# EMG_rev_I.net
KiCad netlist of a schematic drawn in EAGLE
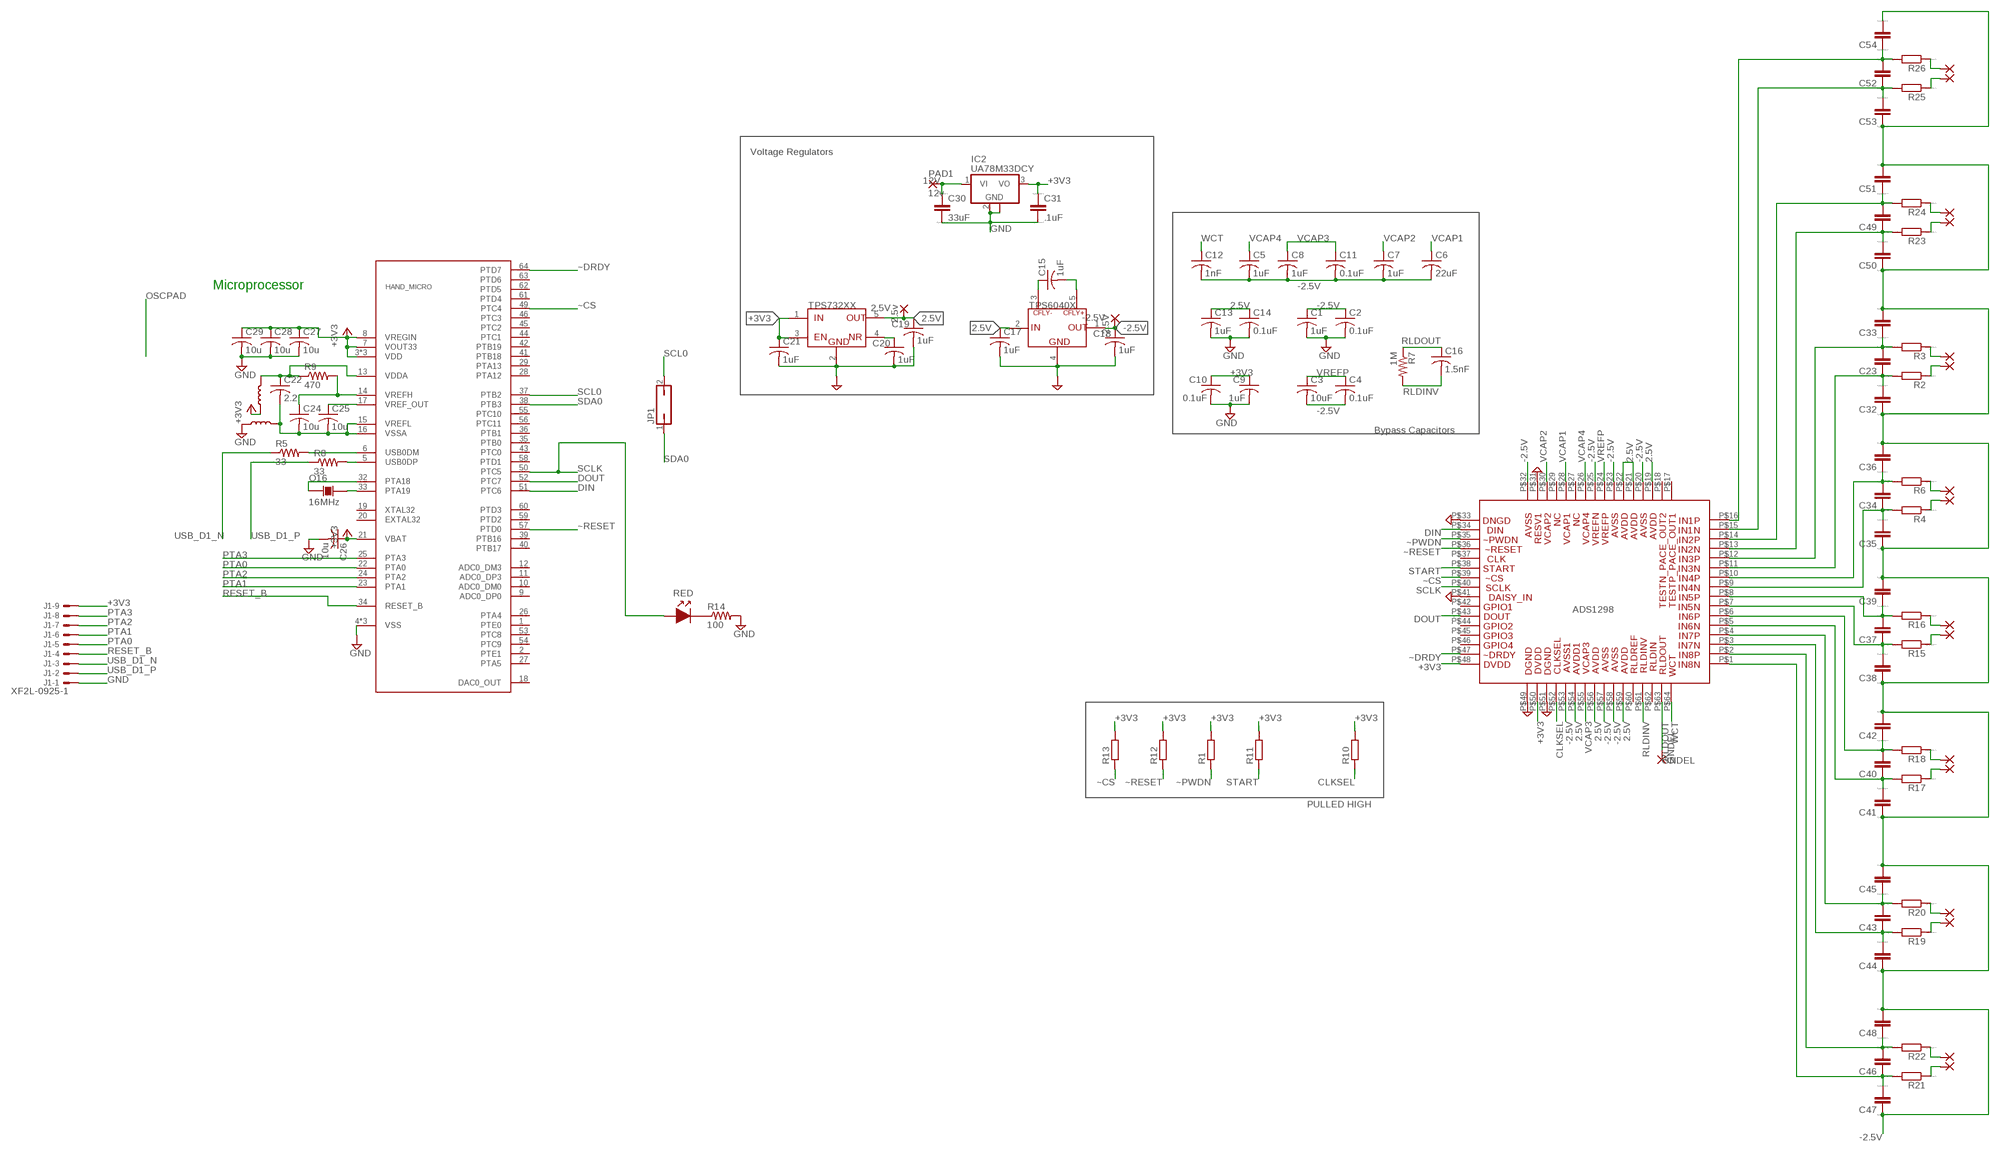
[diagram p0: schematic, sheet 1]

(export (version "E")
  (design (tool "Eeschema 10.0.6"))
  (components
    (comp (ref "-2.5V")
      (value "-2.5V")
      (footprint "eagle-import:2,54_0,9")
      (libsource (lib "eagle-import") (part "2,54/0,9"))
    )
    (comp (ref "2.5V")
      (value "2.5v")
      (footprint "eagle-import:2,54_0,9")
      (libsource (lib "eagle-import") (part "2,54/0,9"))
    )
    (comp (ref "C1")
      (value "1uF")
      (footprint "eagle-import:C0603")
      (libsource (lib "eagle-import") (part "C-USC0603"))
    )
    (comp (ref "C2")
      (value "0.1uF")
      (footprint "eagle-import:C0603")
      (libsource (lib "eagle-import") (part "C-USC0603"))
    )
    (comp (ref "C3")
      (value "10uF")
      (footprint "eagle-import:C0603")
      (libsource (lib "eagle-import") (part "C-USC0603"))
    )
    (comp (ref "C4")
      (value "0.1uF")
      (footprint "eagle-import:C0603")
      (libsource (lib "eagle-import") (part "C-USC0603"))
    )
    (comp (ref "C5")
      (value "1uF")
      (footprint "eagle-import:C0603")
      (libsource (lib "eagle-import") (part "C-USC0603"))
    )
    (comp (ref "C6")
      (value "22uF")
      (footprint "eagle-import:C0603")
      (libsource (lib "eagle-import") (part "C-USC0603"))
    )
    (comp (ref "C7")
      (value "1uF")
      (footprint "eagle-import:C0603")
      (libsource (lib "eagle-import") (part "C-USC0603"))
    )
    (comp (ref "C8")
      (value "1uF")
      (footprint "eagle-import:C0603")
      (libsource (lib "eagle-import") (part "C-USC0603"))
    )
    (comp (ref "C9")
      (value "1uF")
      (footprint "eagle-import:C0603")
      (libsource (lib "eagle-import") (part "C-USC0603"))
    )
    (comp (ref "C10")
      (value "0.1uF")
      (footprint "eagle-import:C0603")
      (libsource (lib "eagle-import") (part "C-USC0603"))
    )
    (comp (ref "C11")
      (value "0.1uF")
      (footprint "eagle-import:C0603")
      (libsource (lib "eagle-import") (part "C-USC0603"))
    )
    (comp (ref "C12")
      (value "1nF")
      (footprint "eagle-import:C0603")
      (libsource (lib "eagle-import") (part "C-USC0603"))
    )
    (comp (ref "C13")
      (value "1uF")
      (footprint "eagle-import:C0603")
      (libsource (lib "eagle-import") (part "C-USC0603"))
    )
    (comp (ref "C14")
      (value "0.1uF")
      (footprint "eagle-import:C0603")
      (libsource (lib "eagle-import") (part "C-USC0603"))
    )
    (comp (ref "C15")
      (value "1uF")
      (footprint "eagle-import:C0603")
      (libsource (lib "eagle-import") (part "C-USC0603"))
    )
    (comp (ref "C16")
      (value "1.5nF")
      (footprint "eagle-import:C0603")
      (libsource (lib "eagle-import") (part "C-USC0603"))
    )
    (comp (ref "C17")
      (value "1uF")
      (footprint "eagle-import:C0603")
      (libsource (lib "eagle-import") (part "C-USC0603"))
    )
    (comp (ref "C18")
      (value "1uF")
      (footprint "eagle-import:C0603")
      (libsource (lib "eagle-import") (part "C-USC0603"))
    )
    (comp (ref "C19")
      (value "1uF")
      (footprint "eagle-import:C0603")
      (libsource (lib "eagle-import") (part "C-USC0603"))
    )
    (comp (ref "C20")
      (value "1uF")
      (footprint "eagle-import:C0603")
      (libsource (lib "eagle-import") (part "C-USC0603"))
    )
    (comp (ref "C21")
      (value "1uF")
      (footprint "eagle-import:C0603")
      (libsource (lib "eagle-import") (part "C-USC0603"))
    )
    (comp (ref "C22")
      (value "2.2")
      (footprint "eagle-import:C0402")
      (libsource (lib "eagle-import") (part "rcl_C-USC0402"))
    )
    (comp (ref "C23")
      (value "CC0402")
      (footprint "eagle-import:C0402")
      (libsource (lib "eagle-import") (part "CC0402"))
    )
    (comp (ref "C24")
      (value "10u")
      (footprint "eagle-import:C0402")
      (libsource (lib "eagle-import") (part "rcl_C-USC0402"))
    )
    (comp (ref "C25")
      (value "10u")
      (footprint "eagle-import:C0402")
      (libsource (lib "eagle-import") (part "rcl_C-USC0402"))
    )
    (comp (ref "C26")
      (value "10u")
      (footprint "eagle-import:C0402")
      (libsource (lib "eagle-import") (part "rcl_C-USC0402"))
    )
    (comp (ref "C27")
      (value "10u")
      (footprint "eagle-import:C0402")
      (libsource (lib "eagle-import") (part "rcl_C-USC0402"))
    )
    (comp (ref "C28")
      (value "10u")
      (footprint "eagle-import:C0402")
      (libsource (lib "eagle-import") (part "rcl_C-USC0402"))
    )
    (comp (ref "C29")
      (value "10u")
      (footprint "eagle-import:C0402")
      (libsource (lib "eagle-import") (part "rcl_C-USC0402"))
    )
    (comp (ref "C30")
      (value "33uF")
      (footprint "eagle-import:C0402")
      (libsource (lib "eagle-import") (part "CC0402"))
    )
    (comp (ref "C31")
      (value ".1uF")
      (footprint "eagle-import:C0402")
      (libsource (lib "eagle-import") (part "CC0402"))
    )
    (comp (ref "C32")
      (value "CC0402")
      (footprint "eagle-import:C0402")
      (libsource (lib "eagle-import") (part "CC0402"))
    )
    (comp (ref "C33")
      (value "CC0402")
      (footprint "eagle-import:C0402")
      (libsource (lib "eagle-import") (part "CC0402"))
    )
    (comp (ref "C34")
      (value "CC0402")
      (footprint "eagle-import:C0402")
      (libsource (lib "eagle-import") (part "CC0402"))
    )
    (comp (ref "C35")
      (value "CC0402")
      (footprint "eagle-import:C0402")
      (libsource (lib "eagle-import") (part "CC0402"))
    )
    (comp (ref "C36")
      (value "CC0402")
      (footprint "eagle-import:C0402")
      (libsource (lib "eagle-import") (part "CC0402"))
    )
    (comp (ref "C37")
      (value "CC0402")
      (footprint "eagle-import:C0402")
      (libsource (lib "eagle-import") (part "CC0402"))
    )
    (comp (ref "C38")
      (value "CC0402")
      (footprint "eagle-import:C0402")
      (libsource (lib "eagle-import") (part "CC0402"))
    )
    (comp (ref "C39")
      (value "CC0402")
      (footprint "eagle-import:C0402")
      (libsource (lib "eagle-import") (part "CC0402"))
    )
    (comp (ref "C40")
      (value "CC0402")
      (footprint "eagle-import:C0402")
      (libsource (lib "eagle-import") (part "CC0402"))
    )
    (comp (ref "C41")
      (value "CC0402")
      (footprint "eagle-import:C0402")
      (libsource (lib "eagle-import") (part "CC0402"))
    )
    (comp (ref "C42")
      (value "CC0402")
      (footprint "eagle-import:C0402")
      (libsource (lib "eagle-import") (part "CC0402"))
    )
    (comp (ref "C43")
      (value "CC0402")
      (footprint "eagle-import:C0402")
      (libsource (lib "eagle-import") (part "CC0402"))
    )
    (comp (ref "C44")
      (value "CC0402")
      (footprint "eagle-import:C0402")
      (libsource (lib "eagle-import") (part "CC0402"))
    )
    (comp (ref "C45")
      (value "CC0402")
      (footprint "eagle-import:C0402")
      (libsource (lib "eagle-import") (part "CC0402"))
    )
    (comp (ref "C46")
      (value "CC0402")
      (footprint "eagle-import:C0402")
      (libsource (lib "eagle-import") (part "CC0402"))
    )
    (comp (ref "C47")
      (value "CC0402")
      (footprint "eagle-import:C0402")
      (libsource (lib "eagle-import") (part "CC0402"))
    )
    (comp (ref "C48")
      (value "CC0402")
      (footprint "eagle-import:C0402")
      (libsource (lib "eagle-import") (part "CC0402"))
    )
    (comp (ref "C49")
      (value "CC0402")
      (footprint "eagle-import:C0402")
      (libsource (lib "eagle-import") (part "CC0402"))
    )
    (comp (ref "C50")
      (value "CC0402")
      (footprint "eagle-import:C0402")
      (libsource (lib "eagle-import") (part "CC0402"))
    )
    (comp (ref "C51")
      (value "CC0402")
      (footprint "eagle-import:C0402")
      (libsource (lib "eagle-import") (part "CC0402"))
    )
    (comp (ref "C52")
      (value "CC0402")
      (footprint "eagle-import:C0402")
      (libsource (lib "eagle-import") (part "CC0402"))
    )
    (comp (ref "C53")
      (value "CC0402")
      (footprint "eagle-import:C0402")
      (libsource (lib "eagle-import") (part "CC0402"))
    )
    (comp (ref "C54")
      (value "CC0402")
      (footprint "eagle-import:C0402")
      (libsource (lib "eagle-import") (part "CC0402"))
    )
    (comp (ref "GNDEL")
      (value "GNDEL")
      (footprint "eagle-import:2,54_0,9")
      (libsource (lib "eagle-import") (part "2,54/0,9"))
    )
    (comp (ref "HAND_MICRO")
      (value "MK20DX256VLH7")
      (footprint "eagle-import:LQFP-64-10-10")
      (libsource (lib "eagle-import") (part "MK20DX256VLH7"))
    )
    (comp (ref "IC2")
      (value "UA78M33DCY")
      (footprint "eagle-import:SOT223")
      (libsource (lib "eagle-import") (part "UA78MDCY33"))
    )
    (comp (ref "J1")
      (value "XF2L-0925-1")
      (footprint "eagle-import:XF2L-0925-1")
      (fields (field (name "MPN") "XF2L-0925-1A"))
      (libsource (lib "eagle-import") (part "XF2-09?25-1L"))
    )
    (comp (ref "JP1")
      (value "JP1Q")
      (footprint "eagle-import:JP1")
      (libsource (lib "eagle-import") (part "JP1Q"))
    )
    (comp (ref "O16")
      (value "16MHz")
      (footprint "eagle-import:NX3225SA")
      (libsource (lib "eagle-import") (part "NX3225SA"))
    )
    (comp (ref "PAD1")
      (value "12v")
      (footprint "eagle-import:2,54_0,9")
      (libsource (lib "eagle-import") (part "2,54/0,9"))
    )
    (comp (ref "R1")
      (value "RR0402")
      (footprint "eagle-import:R0402")
      (libsource (lib "eagle-import") (part "RR0402"))
    )
    (comp (ref "R2")
      (value "RR0402")
      (footprint "eagle-import:R0402")
      (libsource (lib "eagle-import") (part "RR0402"))
    )
    (comp (ref "R3")
      (value "RR0402")
      (footprint "eagle-import:R0402")
      (libsource (lib "eagle-import") (part "RR0402"))
    )
    (comp (ref "R4")
      (value "RR0402")
      (footprint "eagle-import:R0402")
      (libsource (lib "eagle-import") (part "RR0402"))
    )
    (comp (ref "R5")
      (value "33")
      (footprint "eagle-import:R0402")
      (libsource (lib "eagle-import") (part "rcl_R-US_R0402"))
    )
    (comp (ref "R6")
      (value "RR0402")
      (footprint "eagle-import:R0402")
      (libsource (lib "eagle-import") (part "RR0402"))
    )
    (comp (ref "R7")
      (value "1M")
      (footprint "eagle-import:R0603")
      (libsource (lib "eagle-import") (part "R-US_R0603"))
    )
    (comp (ref "R8")
      (value "33")
      (footprint "eagle-import:R0402")
      (libsource (lib "eagle-import") (part "rcl_R-US_R0402"))
    )
    (comp (ref "R9")
      (value "470")
      (footprint "eagle-import:R0402")
      (libsource (lib "eagle-import") (part "rcl_R-US_R0402"))
    )
    (comp (ref "R10")
      (value "RR0402")
      (footprint "eagle-import:R0402")
      (libsource (lib "eagle-import") (part "RR0402"))
    )
    (comp (ref "R11")
      (value "RR0402")
      (footprint "eagle-import:R0402")
      (libsource (lib "eagle-import") (part "RR0402"))
    )
    (comp (ref "R12")
      (value "RR0402")
      (footprint "eagle-import:R0402")
      (libsource (lib "eagle-import") (part "RR0402"))
    )
    (comp (ref "R13")
      (value "RR0402")
      (footprint "eagle-import:R0402")
      (libsource (lib "eagle-import") (part "RR0402"))
    )
    (comp (ref "R14")
      (value "100")
      (footprint "eagle-import:R0603")
      (libsource (lib "eagle-import") (part "rcl_R-US_R0603"))
    )
    (comp (ref "R15")
      (value "RR0402")
      (footprint "eagle-import:R0402")
      (libsource (lib "eagle-import") (part "RR0402"))
    )
    (comp (ref "R16")
      (value "RR0402")
      (footprint "eagle-import:R0402")
      (libsource (lib "eagle-import") (part "RR0402"))
    )
    (comp (ref "R17")
      (value "RR0402")
      (footprint "eagle-import:R0402")
      (libsource (lib "eagle-import") (part "RR0402"))
    )
    (comp (ref "R18")
      (value "RR0402")
      (footprint "eagle-import:R0402")
      (libsource (lib "eagle-import") (part "RR0402"))
    )
    (comp (ref "R19")
      (value "RR0402")
      (footprint "eagle-import:R0402")
      (libsource (lib "eagle-import") (part "RR0402"))
    )
    (comp (ref "R20")
      (value "RR0402")
      (footprint "eagle-import:R0402")
      (libsource (lib "eagle-import") (part "RR0402"))
    )
    (comp (ref "R21")
      (value "RR0402")
      (footprint "eagle-import:R0402")
      (libsource (lib "eagle-import") (part "RR0402"))
    )
    (comp (ref "R22")
      (value "RR0402")
      (footprint "eagle-import:R0402")
      (libsource (lib "eagle-import") (part "RR0402"))
    )
    (comp (ref "R23")
      (value "RR0402")
      (footprint "eagle-import:R0402")
      (libsource (lib "eagle-import") (part "RR0402"))
    )
    (comp (ref "R24")
      (value "RR0402")
      (footprint "eagle-import:R0402")
      (libsource (lib "eagle-import") (part "RR0402"))
    )
    (comp (ref "R25")
      (value "RR0402")
      (footprint "eagle-import:R0402")
      (libsource (lib "eagle-import") (part "RR0402"))
    )
    (comp (ref "R26")
      (value "RR0402")
      (footprint "eagle-import:R0402")
      (libsource (lib "eagle-import") (part "RR0402"))
    )
    (comp (ref "RED")
      (value "LED0603")
      (footprint "eagle-import:L0603")
      (libsource (lib "eagle-import") (part "LED0603"))
    )
    (comp (ref "U$1")
      (value "ADS1298")
      (footprint "eagle-import:TQFP-64")
      (libsource (lib "eagle-import") (part "ADS1298"))
    )
    (comp (ref "U$2")
      (value "FERRITE600OHM100MHZ")
      (footprint "eagle-import:L0603")
      (libsource (lib "eagle-import") (part "FERRITE600OHM100MHZ"))
    )
    (comp (ref "U$3")
      (value "TPS6040X")
      (footprint "eagle-import:SOT23-5")
      (libsource (lib "eagle-import") (part "TPS6040X"))
    )
    (comp (ref "U$4")
      (value "TPS732XX")
      (footprint "eagle-import:SOT23-5")
      (libsource (lib "eagle-import") (part "TPS732XX"))
    )
    (comp (ref "U$12")
      (value "2X1,6/0,9")
      (footprint "eagle-import:2X1,6_0,9")
      (libsource (lib "eagle-import") (part "2X1,6/0,9"))
    )
    (comp (ref "U$13")
      (value "FERRITE600OHM100MHZ")
      (footprint "eagle-import:L0603")
      (libsource (lib "eagle-import") (part "FERRITE600OHM100MHZ"))
    )
    (comp (ref "U$14")
      (value "2X1,6/0,9")
      (footprint "eagle-import:2X1,6_0,9")
      (libsource (lib "eagle-import") (part "2X1,6/0,9"))
    )
    (comp (ref "U$15")
      (value "2X1,6/0,9")
      (footprint "eagle-import:2X1,6_0,9")
      (libsource (lib "eagle-import") (part "2X1,6/0,9"))
    )
    (comp (ref "U$16")
      (value "2X1,6/0,9")
      (footprint "eagle-import:2X1,6_0,9")
      (libsource (lib "eagle-import") (part "2X1,6/0,9"))
    )
    (comp (ref "U$17")
      (value "2X1,6/0,9")
      (footprint "eagle-import:2X1,6_0,9")
      (libsource (lib "eagle-import") (part "2X1,6/0,9"))
    )
    (comp (ref "U$18")
      (value "2X1,6/0,9")
      (footprint "eagle-import:2X1,6_0,9")
      (libsource (lib "eagle-import") (part "2X1,6/0,9"))
    )
    (comp (ref "U$19")
      (value "2X1,6/0,9")
      (footprint "eagle-import:2X1,6_0,9")
      (libsource (lib "eagle-import") (part "2X1,6/0,9"))
    )
    (comp (ref "U$20")
      (value "2X1,6/0,9")
      (footprint "eagle-import:2X1,6_0,9")
      (libsource (lib "eagle-import") (part "2X1,6/0,9"))
    )
  )
  (nets
    (net (code "1") (name "+3V3") (class "Default")
      (node (ref "C10") (pin "1") (pinfunction "1_1") (pintype "passive"))
      (node (ref "C21") (pin "1") (pinfunction "1_1") (pintype "passive"))
      (node (ref "C26") (pin "1") (pinfunction "1_1") (pintype "passive"))
      (node (ref "C27") (pin "1") (pinfunction "1_1") (pintype "passive"))
      (node (ref "C28") (pin "1") (pinfunction "1_1") (pintype "passive"))
      (node (ref "C29") (pin "1") (pinfunction "1_1") (pintype "passive"))
      (node (ref "C31") (pin "1") (pinfunction "1_1") (pintype "passive"))
      (node (ref "C9") (pin "1") (pinfunction "1_1") (pintype "passive"))
      (node (ref "HAND_MICRO") (pin "21") (pinfunction "VBAT_21") (pintype "bidirectional"))
      (node (ref "HAND_MICRO") (pin "3") (pinfunction "VDD_3") (pintype "bidirectional"))
      (node (ref "HAND_MICRO") (pin "30") (pinfunction "VDD_30") (pintype "bidirectional"))
      (node (ref "HAND_MICRO") (pin "48") (pinfunction "VDD_48") (pintype "bidirectional"))
      (node (ref "HAND_MICRO") (pin "7") (pinfunction "VOUT33_7") (pintype "bidirectional"))
      (node (ref "HAND_MICRO") (pin "8") (pinfunction "VREGIN_8") (pintype "bidirectional"))
      (node (ref "IC2") (pin "3") (pinfunction "VO_3") (pintype "passive"))
      (node (ref "J1") (pin "9") (pinfunction "MS_9") (pintype "passive"))
      (node (ref "R1") (pin "2") (pinfunction "2_2") (pintype "passive"))
      (node (ref "R10") (pin "2") (pinfunction "2_2") (pintype "passive"))
      (node (ref "R11") (pin "2") (pinfunction "2_2") (pintype "passive"))
      (node (ref "R12") (pin "2") (pinfunction "2_2") (pintype "passive"))
      (node (ref "R13") (pin "2") (pinfunction "2_2") (pintype "passive"))
      (node (ref "U$1") (pin "P$48") (pinfunction "P$48_P$48") (pintype "bidirectional"))
      (node (ref "U$1") (pin "P$50") (pinfunction "P$50_P$50") (pintype "bidirectional"))
      (node (ref "U$13") (pin "1") (pinfunction "P$1_1") (pintype "bidirectional"))
      (node (ref "U$4") (pin "1") (pinfunction "IN_1") (pintype "bidirectional"))
      (node (ref "U$4") (pin "3") (pinfunction "EN_3") (pintype "bidirectional"))
    )
    (net (code "2") (name "-2.5V") (class "Default")
      (node (ref "-2.5V") (pin "1") (pinfunction "P_1") (pintype "passive"))
      (node (ref "C1") (pin "1") (pinfunction "1_1") (pintype "passive"))
      (node (ref "C11") (pin "2") (pinfunction "2_2") (pintype "passive"))
      (node (ref "C12") (pin "2") (pinfunction "2_2") (pintype "passive"))
      (node (ref "C18") (pin "1") (pinfunction "1_1") (pintype "passive"))
      (node (ref "C2") (pin "1") (pinfunction "1_1") (pintype "passive"))
      (node (ref "C3") (pin "2") (pinfunction "2_2") (pintype "passive"))
      (node (ref "C32") (pin "1") (pinfunction "1_1") (pintype "passive"))
      (node (ref "C33") (pin "2") (pinfunction "2_2") (pintype "passive"))
      (node (ref "C35") (pin "1") (pinfunction "1_1") (pintype "passive"))
      (node (ref "C36") (pin "2") (pinfunction "2_2") (pintype "passive"))
      (node (ref "C38") (pin "1") (pinfunction "1_1") (pintype "passive"))
      (node (ref "C39") (pin "2") (pinfunction "2_2") (pintype "passive"))
      (node (ref "C4") (pin "2") (pinfunction "2_2") (pintype "passive"))
      (node (ref "C41") (pin "1") (pinfunction "1_1") (pintype "passive"))
      (node (ref "C42") (pin "2") (pinfunction "2_2") (pintype "passive"))
      (node (ref "C44") (pin "1") (pinfunction "1_1") (pintype "passive"))
      (node (ref "C45") (pin "2") (pinfunction "2_2") (pintype "passive"))
      (node (ref "C47") (pin "1") (pinfunction "1_1") (pintype "passive"))
      (node (ref "C48") (pin "2") (pinfunction "2_2") (pintype "passive"))
      (node (ref "C5") (pin "2") (pinfunction "2_2") (pintype "passive"))
      (node (ref "C50") (pin "1") (pinfunction "1_1") (pintype "passive"))
      (node (ref "C51") (pin "2") (pinfunction "2_2") (pintype "passive"))
      (node (ref "C53") (pin "1") (pinfunction "1_1") (pintype "passive"))
      (node (ref "C54") (pin "2") (pinfunction "2_2") (pintype "passive"))
      (node (ref "C6") (pin "2") (pinfunction "2_2") (pintype "passive"))
      (node (ref "C7") (pin "2") (pinfunction "2_2") (pintype "passive"))
      (node (ref "C8") (pin "2") (pinfunction "2_2") (pintype "passive"))
      (node (ref "U$1") (pin "P$20") (pinfunction "P$20_P$20") (pintype "bidirectional"))
      (node (ref "U$1") (pin "P$23") (pinfunction "P$23_P$23") (pintype "bidirectional"))
      (node (ref "U$1") (pin "P$25") (pinfunction "P$25_P$25") (pintype "bidirectional"))
      (node (ref "U$1") (pin "P$32") (pinfunction "P$32_P$32") (pintype "bidirectional"))
      (node (ref "U$1") (pin "P$53") (pinfunction "P$53_P$53") (pintype "bidirectional"))
      (node (ref "U$1") (pin "P$57") (pinfunction "P$57_P$57") (pintype "bidirectional"))
      (node (ref "U$1") (pin "P$58") (pinfunction "P$58_P$58") (pintype "bidirectional"))
      (node (ref "U$3") (pin "1") (pinfunction "OUT_1") (pintype "output"))
    )
    (net (code "3") (name "/12V") (class "Default")
      (node (ref "C30") (pin "1") (pinfunction "1_1") (pintype "passive"))
      (node (ref "IC2") (pin "1") (pinfunction "VI_1") (pintype "input"))
      (node (ref "PAD1") (pin "1") (pinfunction "P_1") (pintype "passive"))
    )
    (net (code "4") (name "/CLKSEL") (class "Default")
      (node (ref "R10") (pin "1") (pinfunction "1_1") (pintype "passive"))
      (node (ref "U$1") (pin "P$52") (pinfunction "P$52_P$52") (pintype "bidirectional"))
    )
    (net (code "5") (name "/DIN") (class "Default")
      (node (ref "HAND_MICRO") (pin "51") (pinfunction "PTC6_51") (pintype "bidirectional"))
      (node (ref "U$1") (pin "P$34") (pinfunction "P$34_P$34") (pintype "bidirectional"))
    )
    (net (code "6") (name "/DOUT") (class "Default")
      (node (ref "HAND_MICRO") (pin "52") (pinfunction "PTC7_52") (pintype "bidirectional"))
      (node (ref "U$1") (pin "P$43") (pinfunction "P$43_P$43") (pintype "bidirectional"))
    )
    (net (code "8") (name "/PTA0") (class "Default")
      (node (ref "HAND_MICRO") (pin "22") (pinfunction "PTA0_22") (pintype "bidirectional"))
      (node (ref "J1") (pin "5") (pinfunction "MS_5") (pintype "passive"))
    )
    (net (code "9") (name "/PTA1") (class "Default")
      (node (ref "HAND_MICRO") (pin "23") (pinfunction "PTA1_23") (pintype "bidirectional"))
      (node (ref "J1") (pin "6") (pinfunction "MS_6") (pintype "passive"))
    )
    (net (code "10") (name "/PTA2") (class "Default")
      (node (ref "HAND_MICRO") (pin "24") (pinfunction "PTA2_24") (pintype "bidirectional"))
      (node (ref "J1") (pin "7") (pinfunction "MS_7") (pintype "passive"))
    )
    (net (code "11") (name "/PTA3") (class "Default")
      (node (ref "HAND_MICRO") (pin "25") (pinfunction "PTA3_25") (pintype "bidirectional"))
      (node (ref "J1") (pin "8") (pinfunction "MS_8") (pintype "passive"))
    )
    (net (code "12") (name "/RESET_B") (class "Default")
      (node (ref "HAND_MICRO") (pin "34") (pinfunction "RESET_B_34") (pintype "bidirectional"))
      (node (ref "J1") (pin "4") (pinfunction "MS_4") (pintype "passive"))
    )
    (net (code "13") (name "/RLDINV") (class "Default")
      (node (ref "C16") (pin "2") (pinfunction "2_2") (pintype "passive"))
      (node (ref "R7") (pin "2") (pinfunction "2_2") (pintype "passive"))
      (node (ref "U$1") (pin "P$61") (pinfunction "P$61_P$61") (pintype "bidirectional"))
    )
    (net (code "14") (name "/RLDOUT") (class "Default")
      (node (ref "C16") (pin "1") (pinfunction "1_1") (pintype "passive"))
      (node (ref "GNDEL") (pin "1") (pinfunction "P_1") (pintype "passive"))
      (node (ref "R7") (pin "1") (pinfunction "1_1") (pintype "passive"))
      (node (ref "U$1") (pin "P$63") (pinfunction "P$63_P$63") (pintype "bidirectional"))
    )
    (net (code "15") (name "/SCL0") (class "Default")
      (node (ref "HAND_MICRO") (pin "37") (pinfunction "PTB2_37") (pintype "bidirectional"))
      (node (ref "JP1") (pin "2") (pinfunction "2_2") (pintype "passive"))
    )
    (net (code "16") (name "/SCLK") (class "Default")
      (node (ref "HAND_MICRO") (pin "50") (pinfunction "PTC5_50") (pintype "bidirectional"))
      (node (ref "RED") (pin "1") (pinfunction "P$1_1") (pintype "bidirectional"))
      (node (ref "U$1") (pin "P$40") (pinfunction "P$40_P$40") (pintype "bidirectional"))
    )
    (net (code "17") (name "/SDA0") (class "Default")
      (node (ref "HAND_MICRO") (pin "38") (pinfunction "PTB3_38") (pintype "bidirectional"))
      (node (ref "JP1") (pin "1") (pinfunction "1_1") (pintype "passive"))
    )
    (net (code "18") (name "/START") (class "Default")
      (node (ref "R11") (pin "1") (pinfunction "1_1") (pintype "passive"))
      (node (ref "U$1") (pin "P$38") (pinfunction "P$38_P$38") (pintype "bidirectional"))
    )
    (net (code "19") (name "/USB_D1_N") (class "Default")
      (node (ref "J1") (pin "3") (pinfunction "MS_3") (pintype "passive"))
      (node (ref "R5") (pin "1") (pinfunction "1_1") (pintype "passive"))
    )
    (net (code "20") (name "/USB_D1_P") (class "Default")
      (node (ref "J1") (pin "2") (pinfunction "MS_2") (pintype "passive"))
      (node (ref "R8") (pin "1") (pinfunction "1_1") (pintype "passive"))
    )
    (net (code "21") (name "/VCAP1") (class "Default")
      (node (ref "C6") (pin "1") (pinfunction "1_1") (pintype "passive"))
      (node (ref "U$1") (pin "P$28") (pinfunction "P$28_P$28") (pintype "bidirectional"))
    )
    (net (code "22") (name "/VCAP2") (class "Default")
      (node (ref "C7") (pin "1") (pinfunction "1_1") (pintype "passive"))
      (node (ref "U$1") (pin "P$30") (pinfunction "P$30_P$30") (pintype "bidirectional"))
    )
    (net (code "23") (name "/VCAP3") (class "Default")
      (node (ref "C11") (pin "1") (pinfunction "1_1") (pintype "passive"))
      (node (ref "C8") (pin "1") (pinfunction "1_1") (pintype "passive"))
      (node (ref "U$1") (pin "P$55") (pinfunction "P$55_P$55") (pintype "bidirectional"))
    )
    (net (code "24") (name "/VCAP4") (class "Default")
      (node (ref "C5") (pin "1") (pinfunction "1_1") (pintype "passive"))
      (node (ref "U$1") (pin "P$26") (pinfunction "P$26_P$26") (pintype "bidirectional"))
    )
    (net (code "25") (name "/VREFP") (class "Default")
      (node (ref "C3") (pin "1") (pinfunction "1_1") (pintype "passive"))
      (node (ref "C4") (pin "1") (pinfunction "1_1") (pintype "passive"))
      (node (ref "U$1") (pin "P$24") (pinfunction "P$24_P$24") (pintype "bidirectional"))
    )
    (net (code "26") (name "/WCT") (class "Default")
      (node (ref "C12") (pin "1") (pinfunction "1_1") (pintype "passive"))
      (node (ref "U$1") (pin "P$64") (pinfunction "P$64_P$64") (pintype "bidirectional"))
    )
    (net (code "27") (name "/~{CS}") (class "Default")
      (node (ref "HAND_MICRO") (pin "49") (pinfunction "PTC4_49") (pintype "bidirectional"))
      (node (ref "R13") (pin "1") (pinfunction "1_1") (pintype "passive"))
      (node (ref "U$1") (pin "P$39") (pinfunction "P$39_P$39") (pintype "bidirectional"))
    )
    (net (code "28") (name "/~{DRDY}") (class "Default")
      (node (ref "HAND_MICRO") (pin "64") (pinfunction "PTD7_64") (pintype "bidirectional"))
      (node (ref "U$1") (pin "P$47") (pinfunction "P$47_P$47") (pintype "bidirectional"))
    )
    (net (code "29") (name "/~{PWDN}") (class "Default")
      (node (ref "R1") (pin "1") (pinfunction "1_1") (pintype "passive"))
      (node (ref "U$1") (pin "P$35") (pinfunction "P$35_P$35") (pintype "bidirectional"))
    )
    (net (code "30") (name "/~{RESET}") (class "Default")
      (node (ref "HAND_MICRO") (pin "57") (pinfunction "PTD0_57") (pintype "bidirectional"))
      (node (ref "R12") (pin "1") (pinfunction "1_1") (pintype "passive"))
      (node (ref "U$1") (pin "P$36") (pinfunction "P$36_P$36") (pintype "bidirectional"))
    )
    (net (code "31") (name "2.5V") (class "Default")
      (node (ref "2.5V") (pin "1") (pinfunction "P_1") (pintype "passive"))
      (node (ref "C13") (pin "1") (pinfunction "1_1") (pintype "passive"))
      (node (ref "C14") (pin "1") (pinfunction "1_1") (pintype "passive"))
      (node (ref "C17") (pin "1") (pinfunction "1_1") (pintype "passive"))
      (node (ref "C19") (pin "1") (pinfunction "1_1") (pintype "passive"))
      (node (ref "U$1") (pin "P$19") (pinfunction "P$19_P$19") (pintype "bidirectional"))
      (node (ref "U$1") (pin "P$21") (pinfunction "P$21_P$21") (pintype "bidirectional"))
      (node (ref "U$1") (pin "P$22") (pinfunction "P$22_P$22") (pintype "bidirectional"))
      (node (ref "U$1") (pin "P$54") (pinfunction "P$54_P$54") (pintype "bidirectional"))
      (node (ref "U$1") (pin "P$56") (pinfunction "P$56_P$56") (pintype "bidirectional"))
      (node (ref "U$1") (pin "P$59") (pinfunction "P$59_P$59") (pintype "bidirectional"))
      (node (ref "U$3") (pin "2") (pinfunction "IN_2") (pintype "input"))
      (node (ref "U$4") (pin "5") (pinfunction "OUT_5") (pintype "bidirectional"))
    )
    (net (code "32") (name "GND") (class "Default")
      (node (ref "C1") (pin "2") (pinfunction "2_2") (pintype "passive"))
      (node (ref "C10") (pin "2") (pinfunction "2_2") (pintype "passive"))
      (node (ref "C13") (pin "2") (pinfunction "2_2") (pintype "passive"))
      (node (ref "C14") (pin "2") (pinfunction "2_2") (pintype "passive"))
      (node (ref "C17") (pin "2") (pinfunction "2_2") (pintype "passive"))
      (node (ref "C18") (pin "2") (pinfunction "2_2") (pintype "passive"))
      (node (ref "C19") (pin "2") (pinfunction "2_2") (pintype "passive"))
      (node (ref "C2") (pin "2") (pinfunction "2_2") (pintype "passive"))
      (node (ref "C20") (pin "2") (pinfunction "2_2") (pintype "passive"))
      (node (ref "C21") (pin "2") (pinfunction "2_2") (pintype "passive"))
      (node (ref "C26") (pin "2") (pinfunction "2_2") (pintype "passive"))
      (node (ref "C27") (pin "2") (pinfunction "2_2") (pintype "passive"))
      (node (ref "C28") (pin "2") (pinfunction "2_2") (pintype "passive"))
      (node (ref "C29") (pin "2") (pinfunction "2_2") (pintype "passive"))
      (node (ref "C30") (pin "2") (pinfunction "2_2") (pintype "passive"))
      (node (ref "C31") (pin "2") (pinfunction "2_2") (pintype "passive"))
      (node (ref "C9") (pin "2") (pinfunction "2_2") (pintype "passive"))
      (node (ref "HAND_MICRO") (pin "31") (pinfunction "VSS_31") (pintype "bidirectional"))
      (node (ref "HAND_MICRO") (pin "4") (pinfunction "VSS_4") (pintype "bidirectional"))
      (node (ref "HAND_MICRO") (pin "47") (pinfunction "VSS_47") (pintype "bidirectional"))
      (node (ref "IC2") (pin "2") (pinfunction "GND_2") (pintype "passive"))
      (node (ref "IC2") (pin "4") (pinfunction "GND_4") (pintype "passive"))
      (node (ref "J1") (pin "1") (pinfunction "MSV_1") (pintype "passive"))
      (node (ref "R14") (pin "2") (pinfunction "2_2") (pintype "passive"))
      (node (ref "U$1") (pin "P$31") (pinfunction "P$31_P$31") (pintype "bidirectional"))
      (node (ref "U$1") (pin "P$33") (pinfunction "P$33_P$33") (pintype "bidirectional"))
      (node (ref "U$1") (pin "P$41") (pinfunction "P$41_P$41") (pintype "bidirectional"))
      (node (ref "U$1") (pin "P$49") (pinfunction "P$49_P$49") (pintype "bidirectional"))
      (node (ref "U$1") (pin "P$51") (pinfunction "P$51_P$51") (pintype "bidirectional"))
      (node (ref "U$2") (pin "1") (pinfunction "P$1_1") (pintype "bidirectional"))
      (node (ref "U$3") (pin "4") (pinfunction "GND_4") (pintype "power_in"))
      (node (ref "U$4") (pin "2") (pinfunction "GND_2") (pintype "bidirectional"))
    )
    (net (code "33") (name "Net-(C23-Pad1)") (class "Default")
      (node (ref "C23") (pin "1") (pinfunction "1_1") (pintype "passive"))
      (node (ref "C32") (pin "2") (pinfunction "2_2") (pintype "passive"))
      (node (ref "R2") (pin "2") (pinfunction "2_2") (pintype "passive"))
      (node (ref "U$1") (pin "P$11") (pinfunction "P$11_P$11") (pintype "bidirectional"))
    )
    (net (code "34") (name "Net-(C23-Pad2)") (class "Default")
      (node (ref "C23") (pin "2") (pinfunction "2_2") (pintype "passive"))
      (node (ref "C33") (pin "1") (pinfunction "1_1") (pintype "passive"))
      (node (ref "R3") (pin "2") (pinfunction "2_2") (pintype "passive"))
      (node (ref "U$1") (pin "P$12") (pinfunction "P$12_P$12") (pintype "bidirectional"))
    )
    (net (code "35") (name "Net-(C34-Pad1)") (class "Default")
      (node (ref "C34") (pin "1") (pinfunction "1_1") (pintype "passive"))
      (node (ref "C35") (pin "2") (pinfunction "2_2") (pintype "passive"))
      (node (ref "R4") (pin "2") (pinfunction "2_2") (pintype "passive"))
      (node (ref "U$1") (pin "P$9") (pinfunction "P$9_P$9") (pintype "bidirectional"))
    )
    (net (code "36") (name "Net-(C34-Pad2)") (class "Default")
      (node (ref "C34") (pin "2") (pinfunction "2_2") (pintype "passive"))
      (node (ref "C36") (pin "1") (pinfunction "1_1") (pintype "passive"))
      (node (ref "R6") (pin "2") (pinfunction "2_2") (pintype "passive"))
      (node (ref "U$1") (pin "P$10") (pinfunction "P$10_P$10") (pintype "bidirectional"))
    )
    (net (code "37") (name "Net-(C37-Pad1)") (class "Default")
      (node (ref "C37") (pin "1") (pinfunction "1_1") (pintype "passive"))
      (node (ref "C38") (pin "2") (pinfunction "2_2") (pintype "passive"))
      (node (ref "R15") (pin "2") (pinfunction "2_2") (pintype "passive"))
      (node (ref "U$1") (pin "P$7") (pinfunction "P$7_P$7") (pintype "bidirectional"))
    )
    (net (code "38") (name "Net-(C37-Pad2)") (class "Default")
      (node (ref "C37") (pin "2") (pinfunction "2_2") (pintype "passive"))
      (node (ref "C39") (pin "1") (pinfunction "1_1") (pintype "passive"))
      (node (ref "R16") (pin "2") (pinfunction "2_2") (pintype "passive"))
      (node (ref "U$1") (pin "P$8") (pinfunction "P$8_P$8") (pintype "bidirectional"))
    )
    (net (code "39") (name "Net-(C40-Pad1)") (class "Default")
      (node (ref "C40") (pin "1") (pinfunction "1_1") (pintype "passive"))
      (node (ref "C41") (pin "2") (pinfunction "2_2") (pintype "passive"))
      (node (ref "R17") (pin "2") (pinfunction "2_2") (pintype "passive"))
      (node (ref "U$1") (pin "P$5") (pinfunction "P$5_P$5") (pintype "bidirectional"))
    )
    (net (code "40") (name "Net-(C40-Pad2)") (class "Default")
      (node (ref "C40") (pin "2") (pinfunction "2_2") (pintype "passive"))
      (node (ref "C42") (pin "1") (pinfunction "1_1") (pintype "passive"))
      (node (ref "R18") (pin "2") (pinfunction "2_2") (pintype "passive"))
      (node (ref "U$1") (pin "P$6") (pinfunction "P$6_P$6") (pintype "bidirectional"))
    )
    (net (code "41") (name "Net-(C43-Pad1)") (class "Default")
      (node (ref "C43") (pin "1") (pinfunction "1_1") (pintype "passive"))
      (node (ref "C44") (pin "2") (pinfunction "2_2") (pintype "passive"))
      (node (ref "R19") (pin "2") (pinfunction "2_2") (pintype "passive"))
      (node (ref "U$1") (pin "P$3") (pinfunction "P$3_P$3") (pintype "bidirectional"))
    )
    (net (code "42") (name "Net-(C43-Pad2)") (class "Default")
      (node (ref "C43") (pin "2") (pinfunction "2_2") (pintype "passive"))
      (node (ref "C45") (pin "1") (pinfunction "1_1") (pintype "passive"))
      (node (ref "R20") (pin "2") (pinfunction "2_2") (pintype "passive"))
      (node (ref "U$1") (pin "P$4") (pinfunction "P$4_P$4") (pintype "bidirectional"))
    )
    (net (code "43") (name "Net-(C46-Pad1)") (class "Default")
      (node (ref "C46") (pin "1") (pinfunction "1_1") (pintype "passive"))
      (node (ref "C47") (pin "2") (pinfunction "2_2") (pintype "passive"))
      (node (ref "R21") (pin "2") (pinfunction "2_2") (pintype "passive"))
      (node (ref "U$1") (pin "P$1") (pinfunction "P$1_P$1") (pintype "bidirectional"))
    )
    (net (code "44") (name "Net-(C46-Pad2)") (class "Default")
      (node (ref "C46") (pin "2") (pinfunction "2_2") (pintype "passive"))
      (node (ref "C48") (pin "1") (pinfunction "1_1") (pintype "passive"))
      (node (ref "R22") (pin "2") (pinfunction "2_2") (pintype "passive"))
      (node (ref "U$1") (pin "P$2") (pinfunction "P$2_P$2") (pintype "bidirectional"))
    )
    (net (code "45") (name "Net-(C49-Pad1)") (class "Default")
      (node (ref "C49") (pin "1") (pinfunction "1_1") (pintype "passive"))
      (node (ref "C50") (pin "2") (pinfunction "2_2") (pintype "passive"))
      (node (ref "R23") (pin "2") (pinfunction "2_2") (pintype "passive"))
      (node (ref "U$1") (pin "P$13") (pinfunction "P$13_P$13") (pintype "bidirectional"))
    )
    (net (code "46") (name "Net-(C49-Pad2)") (class "Default")
      (node (ref "C49") (pin "2") (pinfunction "2_2") (pintype "passive"))
      (node (ref "C51") (pin "1") (pinfunction "1_1") (pintype "passive"))
      (node (ref "R24") (pin "2") (pinfunction "2_2") (pintype "passive"))
      (node (ref "U$1") (pin "P$14") (pinfunction "P$14_P$14") (pintype "bidirectional"))
    )
    (net (code "47") (name "Net-(C52-Pad1)") (class "Default")
      (node (ref "C52") (pin "1") (pinfunction "1_1") (pintype "passive"))
      (node (ref "C53") (pin "2") (pinfunction "2_2") (pintype "passive"))
      (node (ref "R25") (pin "2") (pinfunction "2_2") (pintype "passive"))
      (node (ref "U$1") (pin "P$15") (pinfunction "P$15_P$15") (pintype "bidirectional"))
    )
    (net (code "48") (name "Net-(C52-Pad2)") (class "Default")
      (node (ref "C52") (pin "2") (pinfunction "2_2") (pintype "passive"))
      (node (ref "C54") (pin "1") (pinfunction "1_1") (pintype "passive"))
      (node (ref "R26") (pin "2") (pinfunction "2_2") (pintype "passive"))
      (node (ref "U$1") (pin "P$16") (pinfunction "P$16_P$16") (pintype "bidirectional"))
    )
    (net (code "49") (name "Net-(HAND_MICRO-PTA18)") (class "Default")
      (node (ref "HAND_MICRO") (pin "32") (pinfunction "PTA18_32") (pintype "bidirectional"))
      (node (ref "O16") (pin "1") (pinfunction "P$1_1") (pintype "bidirectional"))
    )
    (net (code "50") (name "Net-(HAND_MICRO-PTA19)") (class "Default")
      (node (ref "HAND_MICRO") (pin "33") (pinfunction "PTA19_33") (pintype "bidirectional"))
      (node (ref "O16") (pin "3") (pinfunction "P$2_3") (pintype "bidirectional"))
    )
    (net (code "51") (name "Net-(HAND_MICRO-USB0DM)") (class "Default")
      (node (ref "HAND_MICRO") (pin "6") (pinfunction "USB0DM_6") (pintype "bidirectional"))
      (node (ref "R5") (pin "2") (pinfunction "2_2") (pintype "passive"))
    )
    (net (code "52") (name "Net-(HAND_MICRO-USB0DP)") (class "Default")
      (node (ref "HAND_MICRO") (pin "5") (pinfunction "USB0DP_5") (pintype "bidirectional"))
      (node (ref "R8") (pin "2") (pinfunction "2_2") (pintype "passive"))
    )
    (net (code "53") (name "Net-(HAND_MICRO-VDDA)") (class "Default")
      (node (ref "C22") (pin "1") (pinfunction "1_1") (pintype "passive"))
      (node (ref "HAND_MICRO") (pin "13") (pinfunction "VDDA_13") (pintype "bidirectional"))
      (node (ref "R9") (pin "1") (pinfunction "1_1") (pintype "passive"))
      (node (ref "U$13") (pin "2") (pinfunction "P$2_2") (pintype "bidirectional"))
    )
    (net (code "54") (name "Net-(HAND_MICRO-VREFH)") (class "Default")
      (node (ref "C24") (pin "1") (pinfunction "1_1") (pintype "passive"))
      (node (ref "HAND_MICRO") (pin "14") (pinfunction "VREFH_14") (pintype "bidirectional"))
      (node (ref "R9") (pin "2") (pinfunction "2_2") (pintype "passive"))
    )
    (net (code "55") (name "Net-(HAND_MICRO-VREFL)") (class "Default")
      (node (ref "C22") (pin "2") (pinfunction "2_2") (pintype "passive"))
      (node (ref "C24") (pin "2") (pinfunction "2_2") (pintype "passive"))
      (node (ref "C25") (pin "2") (pinfunction "2_2") (pintype "passive"))
      (node (ref "HAND_MICRO") (pin "15") (pinfunction "VREFL_15") (pintype "bidirectional"))
      (node (ref "HAND_MICRO") (pin "16") (pinfunction "VSSA_16") (pintype "bidirectional"))
      (node (ref "U$2") (pin "2") (pinfunction "P$2_2") (pintype "bidirectional"))
    )
    (net (code "56") (name "Net-(HAND_MICRO-VREF_OUT)") (class "Default")
      (node (ref "C25") (pin "1") (pinfunction "1_1") (pintype "passive"))
      (node (ref "HAND_MICRO") (pin "17") (pinfunction "VREF_OUT_17") (pintype "bidirectional"))
    )
    (net (code "57") (name "Net-(RED-P$2)") (class "Default")
      (node (ref "R14") (pin "1") (pinfunction "1_1") (pintype "passive"))
      (node (ref "RED") (pin "2") (pinfunction "P$2_2") (pintype "bidirectional"))
    )
    (net (code "58") (name "Net-(U$3-CFLY+)") (class "Default")
      (node (ref "C15") (pin "2") (pinfunction "2_2") (pintype "passive"))
      (node (ref "U$3") (pin "5") (pinfunction "CFLY+_5") (pintype "bidirectional"))
    )
    (net (code "59") (name "Net-(U$3-CFLY-)") (class "Default")
      (node (ref "C15") (pin "1") (pinfunction "1_1") (pintype "passive"))
      (node (ref "U$3") (pin "3") (pinfunction "CFLY-_3") (pintype "bidirectional"))
    )
    (net (code "60") (name "Net-(U$4-NR)") (class "Default")
      (node (ref "C20") (pin "1") (pinfunction "1_1") (pintype "passive"))
      (node (ref "U$4") (pin "4") (pinfunction "NR_4") (pintype "bidirectional"))
    )
    (net (code "61") (name "Net-(U$12-P)") (class "Default")
      (node (ref "R2") (pin "1") (pinfunction "1_1") (pintype "passive"))
      (node (ref "U$12") (pin "1") (pinfunction "P_1") (pintype "passive"))
    )
    (net (code "62") (name "Net-(U$12-P1)") (class "Default")
      (node (ref "R3") (pin "1") (pinfunction "1_1") (pintype "passive"))
      (node (ref "U$12") (pin "2") (pinfunction "P1_2") (pintype "passive"))
    )
    (net (code "63") (name "Net-(U$14-P)") (class "Default")
      (node (ref "R4") (pin "1") (pinfunction "1_1") (pintype "passive"))
      (node (ref "U$14") (pin "1") (pinfunction "P_1") (pintype "passive"))
    )
    (net (code "64") (name "Net-(U$14-P1)") (class "Default")
      (node (ref "R6") (pin "1") (pinfunction "1_1") (pintype "passive"))
      (node (ref "U$14") (pin "2") (pinfunction "P1_2") (pintype "passive"))
    )
    (net (code "65") (name "Net-(U$15-P)") (class "Default")
      (node (ref "R15") (pin "1") (pinfunction "1_1") (pintype "passive"))
      (node (ref "U$15") (pin "1") (pinfunction "P_1") (pintype "passive"))
    )
    (net (code "66") (name "Net-(U$15-P1)") (class "Default")
      (node (ref "R16") (pin "1") (pinfunction "1_1") (pintype "passive"))
      (node (ref "U$15") (pin "2") (pinfunction "P1_2") (pintype "passive"))
    )
    (net (code "67") (name "Net-(U$16-P)") (class "Default")
      (node (ref "R17") (pin "1") (pinfunction "1_1") (pintype "passive"))
      (node (ref "U$16") (pin "1") (pinfunction "P_1") (pintype "passive"))
    )
    (net (code "68") (name "Net-(U$16-P1)") (class "Default")
      (node (ref "R18") (pin "1") (pinfunction "1_1") (pintype "passive"))
      (node (ref "U$16") (pin "2") (pinfunction "P1_2") (pintype "passive"))
    )
    (net (code "69") (name "Net-(U$17-P)") (class "Default")
      (node (ref "R19") (pin "1") (pinfunction "1_1") (pintype "passive"))
      (node (ref "U$17") (pin "1") (pinfunction "P_1") (pintype "passive"))
    )
    (net (code "70") (name "Net-(U$17-P1)") (class "Default")
      (node (ref "R20") (pin "1") (pinfunction "1_1") (pintype "passive"))
      (node (ref "U$17") (pin "2") (pinfunction "P1_2") (pintype "passive"))
    )
    (net (code "71") (name "Net-(U$18-P)") (class "Default")
      (node (ref "R21") (pin "1") (pinfunction "1_1") (pintype "passive"))
      (node (ref "U$18") (pin "1") (pinfunction "P_1") (pintype "passive"))
    )
    (net (code "72") (name "Net-(U$18-P1)") (class "Default")
      (node (ref "R22") (pin "1") (pinfunction "1_1") (pintype "passive"))
      (node (ref "U$18") (pin "2") (pinfunction "P1_2") (pintype "passive"))
    )
    (net (code "73") (name "Net-(U$19-P)") (class "Default")
      (node (ref "R23") (pin "1") (pinfunction "1_1") (pintype "passive"))
      (node (ref "U$19") (pin "1") (pinfunction "P_1") (pintype "passive"))
    )
    (net (code "74") (name "Net-(U$19-P1)") (class "Default")
      (node (ref "R24") (pin "1") (pinfunction "1_1") (pintype "passive"))
      (node (ref "U$19") (pin "2") (pinfunction "P1_2") (pintype "passive"))
    )
    (net (code "75") (name "Net-(U$20-P)") (class "Default")
      (node (ref "R25") (pin "1") (pinfunction "1_1") (pintype "passive"))
      (node (ref "U$20") (pin "1") (pinfunction "P_1") (pintype "passive"))
    )
    (net (code "76") (name "Net-(U$20-P1)") (class "Default")
      (node (ref "R26") (pin "1") (pinfunction "1_1") (pintype "passive"))
      (node (ref "U$20") (pin "2") (pinfunction "P1_2") (pintype "passive"))
    )
    (net (code "77") (name "unconnected-(HAND_MICRO-ADC0_DM0-Pad10)") (class "Default")
      (node (ref "HAND_MICRO") (pin "10") (pinfunction "ADC0_DM0_10") (pintype "bidirectional"))
    )
    (net (code "78") (name "unconnected-(HAND_MICRO-ADC0_DM3-Pad12)") (class "Default")
      (node (ref "HAND_MICRO") (pin "12") (pinfunction "ADC0_DM3_12") (pintype "bidirectional"))
    )
    (net (code "79") (name "unconnected-(HAND_MICRO-ADC0_DP0-Pad9)") (class "Default")
      (node (ref "HAND_MICRO") (pin "9") (pinfunction "ADC0_DP0_9") (pintype "bidirectional"))
    )
    (net (code "80") (name "unconnected-(HAND_MICRO-ADC0_DP3-Pad11)") (class "Default")
      (node (ref "HAND_MICRO") (pin "11") (pinfunction "ADC0_DP3_11") (pintype "bidirectional"))
    )
    (net (code "81") (name "unconnected-(HAND_MICRO-DAC0_OUT-Pad18)") (class "Default")
      (node (ref "HAND_MICRO") (pin "18") (pinfunction "DAC0_OUT_18") (pintype "bidirectional"))
    )
    (net (code "82") (name "unconnected-(HAND_MICRO-EXTAL32-Pad20)") (class "Default")
      (node (ref "HAND_MICRO") (pin "20") (pinfunction "EXTAL32_20") (pintype "bidirectional"))
    )
    (net (code "83") (name "unconnected-(HAND_MICRO-PTA4-Pad26)") (class "Default")
      (node (ref "HAND_MICRO") (pin "26") (pinfunction "PTA4_26") (pintype "bidirectional"))
    )
    (net (code "84") (name "unconnected-(HAND_MICRO-PTA5-Pad27)") (class "Default")
      (node (ref "HAND_MICRO") (pin "27") (pinfunction "PTA5_27") (pintype "bidirectional"))
    )
    (net (code "85") (name "unconnected-(HAND_MICRO-PTA12-Pad28)") (class "Default")
      (node (ref "HAND_MICRO") (pin "28") (pinfunction "PTA12_28") (pintype "bidirectional"))
    )
    (net (code "86") (name "unconnected-(HAND_MICRO-PTA13-Pad29)") (class "Default")
      (node (ref "HAND_MICRO") (pin "29") (pinfunction "PTA13_29") (pintype "bidirectional"))
    )
    (net (code "87") (name "unconnected-(HAND_MICRO-PTB0-Pad35)") (class "Default")
      (node (ref "HAND_MICRO") (pin "35") (pinfunction "PTB0_35") (pintype "bidirectional"))
    )
    (net (code "88") (name "unconnected-(HAND_MICRO-PTB1-Pad36)") (class "Default")
      (node (ref "HAND_MICRO") (pin "36") (pinfunction "PTB1_36") (pintype "bidirectional"))
    )
    (net (code "89") (name "unconnected-(HAND_MICRO-PTB16-Pad39)") (class "Default")
      (node (ref "HAND_MICRO") (pin "39") (pinfunction "PTB16_39") (pintype "bidirectional"))
    )
    (net (code "90") (name "unconnected-(HAND_MICRO-PTB17-Pad40)") (class "Default")
      (node (ref "HAND_MICRO") (pin "40") (pinfunction "PTB17_40") (pintype "bidirectional"))
    )
    (net (code "91") (name "unconnected-(HAND_MICRO-PTB18-Pad41)") (class "Default")
      (node (ref "HAND_MICRO") (pin "41") (pinfunction "PTB18_41") (pintype "bidirectional"))
    )
    (net (code "92") (name "unconnected-(HAND_MICRO-PTB19-Pad42)") (class "Default")
      (node (ref "HAND_MICRO") (pin "42") (pinfunction "PTB19_42") (pintype "bidirectional"))
    )
    (net (code "93") (name "unconnected-(HAND_MICRO-PTC0-Pad43)") (class "Default")
      (node (ref "HAND_MICRO") (pin "43") (pinfunction "PTC0_43") (pintype "bidirectional"))
    )
    (net (code "94") (name "unconnected-(HAND_MICRO-PTC1-Pad44)") (class "Default")
      (node (ref "HAND_MICRO") (pin "44") (pinfunction "PTC1_44") (pintype "bidirectional"))
    )
    (net (code "95") (name "unconnected-(HAND_MICRO-PTC2-Pad45)") (class "Default")
      (node (ref "HAND_MICRO") (pin "45") (pinfunction "PTC2_45") (pintype "bidirectional"))
    )
    (net (code "96") (name "unconnected-(HAND_MICRO-PTC3-Pad46)") (class "Default")
      (node (ref "HAND_MICRO") (pin "46") (pinfunction "PTC3_46") (pintype "bidirectional"))
    )
    (net (code "97") (name "unconnected-(HAND_MICRO-PTC8-Pad53)") (class "Default")
      (node (ref "HAND_MICRO") (pin "53") (pinfunction "PTC8_53") (pintype "bidirectional"))
    )
    (net (code "98") (name "unconnected-(HAND_MICRO-PTC9-Pad54)") (class "Default")
      (node (ref "HAND_MICRO") (pin "54") (pinfunction "PTC9_54") (pintype "bidirectional"))
    )
    (net (code "99") (name "unconnected-(HAND_MICRO-PTC10-Pad55)") (class "Default")
      (node (ref "HAND_MICRO") (pin "55") (pinfunction "PTC10_55") (pintype "bidirectional"))
    )
    (net (code "100") (name "unconnected-(HAND_MICRO-PTC11-Pad56)") (class "Default")
      (node (ref "HAND_MICRO") (pin "56") (pinfunction "PTC11_56") (pintype "bidirectional"))
    )
    (net (code "101") (name "unconnected-(HAND_MICRO-PTD1-Pad58)") (class "Default")
      (node (ref "HAND_MICRO") (pin "58") (pinfunction "PTD1_58") (pintype "bidirectional"))
    )
    (net (code "102") (name "unconnected-(HAND_MICRO-PTD2-Pad59)") (class "Default")
      (node (ref "HAND_MICRO") (pin "59") (pinfunction "PTD2_59") (pintype "bidirectional"))
    )
    (net (code "103") (name "unconnected-(HAND_MICRO-PTD3-Pad60)") (class "Default")
      (node (ref "HAND_MICRO") (pin "60") (pinfunction "PTD3_60") (pintype "bidirectional"))
    )
    (net (code "104") (name "unconnected-(HAND_MICRO-PTD4-Pad61)") (class "Default")
      (node (ref "HAND_MICRO") (pin "61") (pinfunction "PTD4_61") (pintype "bidirectional"))
    )
    (net (code "105") (name "unconnected-(HAND_MICRO-PTD5-Pad62)") (class "Default")
      (node (ref "HAND_MICRO") (pin "62") (pinfunction "PTD5_62") (pintype "bidirectional"))
    )
    (net (code "106") (name "unconnected-(HAND_MICRO-PTD6-Pad63)") (class "Default")
      (node (ref "HAND_MICRO") (pin "63") (pinfunction "PTD6_63") (pintype "bidirectional"))
    )
    (net (code "107") (name "unconnected-(HAND_MICRO-PTE0-Pad1)") (class "Default")
      (node (ref "HAND_MICRO") (pin "1") (pinfunction "PTE0_1") (pintype "bidirectional"))
    )
    (net (code "108") (name "unconnected-(HAND_MICRO-PTE1-Pad2)") (class "Default")
      (node (ref "HAND_MICRO") (pin "2") (pinfunction "PTE1_2") (pintype "bidirectional"))
    )
    (net (code "109") (name "unconnected-(HAND_MICRO-XTAL32-Pad19)") (class "Default")
      (node (ref "HAND_MICRO") (pin "19") (pinfunction "XTAL32_19") (pintype "bidirectional"))
    )
    (net (code "110") (name "unconnected-(U$1-PadP$17)") (class "Default")
      (node (ref "U$1") (pin "P$17") (pinfunction "P$17_P$17") (pintype "bidirectional"))
    )
    (net (code "111") (name "unconnected-(U$1-PadP$18)") (class "Default")
      (node (ref "U$1") (pin "P$18") (pinfunction "P$18_P$18") (pintype "bidirectional"))
    )
    (net (code "112") (name "unconnected-(U$1-PadP$27)") (class "Default")
      (node (ref "U$1") (pin "P$27") (pinfunction "P$27_P$27") (pintype "bidirectional"))
    )
    (net (code "113") (name "unconnected-(U$1-PadP$29)") (class "Default")
      (node (ref "U$1") (pin "P$29") (pinfunction "P$29_P$29") (pintype "bidirectional"))
    )
    (net (code "114") (name "unconnected-(U$1-PadP$37)") (class "Default")
      (node (ref "U$1") (pin "P$37") (pinfunction "P$37_P$37") (pintype "bidirectional"))
    )
    (net (code "115") (name "unconnected-(U$1-PadP$42)") (class "Default")
      (node (ref "U$1") (pin "P$42") (pinfunction "P$42_P$42") (pintype "bidirectional"))
    )
    (net (code "116") (name "unconnected-(U$1-PadP$44)") (class "Default")
      (node (ref "U$1") (pin "P$44") (pinfunction "P$44_P$44") (pintype "bidirectional"))
    )
    (net (code "117") (name "unconnected-(U$1-PadP$45)") (class "Default")
      (node (ref "U$1") (pin "P$45") (pinfunction "P$45_P$45") (pintype "bidirectional"))
    )
    (net (code "118") (name "unconnected-(U$1-PadP$46)") (class "Default")
      (node (ref "U$1") (pin "P$46") (pinfunction "P$46_P$46") (pintype "bidirectional"))
    )
    (net (code "119") (name "unconnected-(U$1-PadP$60)") (class "Default")
      (node (ref "U$1") (pin "P$60") (pinfunction "P$60_P$60") (pintype "bidirectional"))
    )
    (net (code "120") (name "unconnected-(U$1-PadP$62)") (class "Default")
      (node (ref "U$1") (pin "P$62") (pinfunction "P$62_P$62") (pintype "bidirectional"))
    )
  )
)
